# Power_Supply.net
KiCad netlist of a schematic drawn in Altium Designer
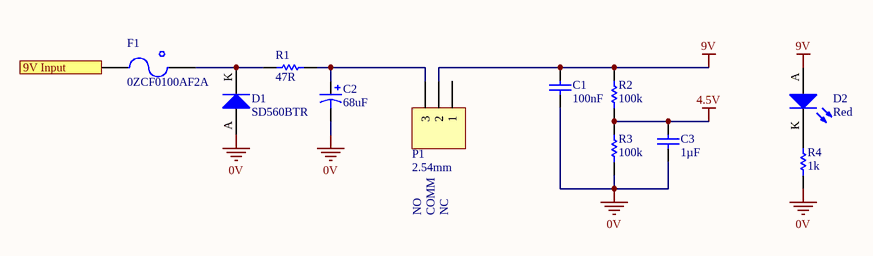
[diagram p0: Power Supply.SchDoc]

(export (version "E")
  (design (tool "Eeschema 10.0.6"))
  (components
    (comp (ref "C1")
      (value "100nF")
      (footprint "0805")
      (fields
        (field (name "PART NUMBER") "GCM21BR71H104KA37L")
        (field (name "TOLERANCE") "±10%")
        (field (name "MANUFACTURER") "muRata")
      )
      (libsource (lib "ts_20-standard-library") (part "Capacitor"))
    )
    (comp (ref "C2")
      (value "~")
      (footprint "2924")
      (fields
        (field (name "PART NUMBER") "TAJV686K035RNJ")
        (field (name "TOLERANCE") "10%")
        (field (name "MANUFACTURER") "AVX Corporation")
      )
      (libsource (lib "ts_20-standard-library") (part "Capacitor (Polarised)"))
    )
    (comp (ref "C3")
      (value "1µF")
      (footprint "0805")
      (fields
        (field (name "PART NUMBER") "GCM21BR71H105KA03L")
        (field (name "TOLERANCE") "±10%")
        (field (name "MANUFACTURER") "muRata")
      )
      (libsource (lib "ts_20-standard-library") (part "Capacitor"))
    )
    (comp (ref "D1")
      (value "SD560BTR")
      (footprint "SMB Diode")
      (description "1.2V_F 600V 5A SMB")
      (fields
        (field (name "MANUFACTURER") "SMC Diode Solutions")
        (field (name "DIGIKEY PART NUMBER") "1655-1530-2-ND")
      )
      (libsource (lib "ts_20-standard-library") (part "Diode"))
    )
    (comp (ref "D2")
      (value "Red")
      (footprint "0805 LED")
      (description "Red LED Indication - Discrete 1.75V 0805 (2012 Metric)")
      (fields (field (name "PART NUMBER") "SML-210LTT86") (field (name "MANUFACTURER") "ROHM Semiconductor"))
      (libsource (lib "ts_20-standard-library") (part "LED"))
    )
    (comp (ref "F1")
      (value "0ZCF0100AF2A")
      (footprint "2920")
      (description "PTC RESET FUSE 60V 1A 292")
      (fields
        (field (name "MANUFACTURER") "Littelfuse Inc.")
        (field (name "DIGIKEY PART NUMBER") "507-2070-1-ND")
      )
      (libsource (lib "ts_20-standard-library") (part "PTC Fuse"))
    )
    (comp (ref "P1")
      (value "2.54mm")
      (footprint "TH 2.54mm Header 1x3")
      (fields (field (name "PART NUMBER") "TH 2.54mm Header 1x3") (field (name "CONTACT") "NA"))
      (libsource (lib "ts_20-standard-connectors") (part "Header 1x3"))
    )
    (comp (ref "R1")
      (value "47R")
      (footprint "2512")
      (fields
        (field (name "PART NUMBER") "352147RFT")
        (field (name "MANUFACTURER") "TE Connectivity")
        (field (name "TOLERANCE") "0.01")
      )
      (libsource (lib "ts_20-standard-library") (part "Resistor"))
    )
    (comp (ref "R2")
      (value "100k")
      (footprint "0805")
      (fields
        (field (name "PART NUMBER") "RC0805FR07100KL")
        (field (name "MANUFACTURER") "YAGEO")
        (field (name "TOLERANCE") "0.01")
      )
      (libsource (lib "ts_20-standard-library") (part "Resistor"))
    )
    (comp (ref "R3")
      (value "100k")
      (footprint "0805")
      (fields
        (field (name "PART NUMBER") "RC0805FR07100KL")
        (field (name "MANUFACTURER") "YAGEO")
        (field (name "TOLERANCE") "0.01")
      )
      (libsource (lib "ts_20-standard-library") (part "Resistor"))
    )
    (comp (ref "R4")
      (value "1k")
      (footprint "0805")
      (fields
        (field (name "PART NUMBER") "RC0805FR071KL")
        (field (name "MANUFACTURER") "YAGEO")
        (field (name "TOLERANCE") "0.01")
      )
      (libsource (lib "ts_20-standard-library") (part "Resistor"))
    )
  )
  (nets
    (net (code "1") (name "/9V Input") (class "Default")
      (node (ref "F1") (pin "1") (pinfunction "1_1") (pintype "passive"))
    )
    (net (code "2") (name "0V") (class "Default")
      (node (ref "C1") (pin "2") (pinfunction "2_2") (pintype "passive"))
      (node (ref "C2") (pin "1") (pinfunction "1_1") (pintype "passive"))
      (node (ref "C3") (pin "1") (pinfunction "1_1") (pintype "passive"))
      (node (ref "D1") (pin "A") (pinfunction "A_A") (pintype "passive"))
      (node (ref "R3") (pin "1") (pinfunction "1_1") (pintype "passive"))
      (node (ref "R4") (pin "1") (pinfunction "1_1") (pintype "passive"))
    )
    (net (code "3") (name "4.5V") (class "Default")
      (node (ref "C3") (pin "2") (pinfunction "2_2") (pintype "passive"))
      (node (ref "R2") (pin "1") (pinfunction "1_1") (pintype "passive"))
      (node (ref "R3") (pin "2") (pinfunction "2_2") (pintype "passive"))
    )
    (net (code "4") (name "9V") (class "Default")
      (node (ref "C1") (pin "1") (pinfunction "1_1") (pintype "passive"))
      (node (ref "D2") (pin "A") (pinfunction "A_A") (pintype "passive"))
      (node (ref "P1") (pin "2") (pinfunction "2_2") (pintype "passive"))
      (node (ref "R2") (pin "2") (pinfunction "2_2") (pintype "passive"))
    )
    (net (code "5") (name "Net-(C2-Pad2)") (class "Default")
      (node (ref "C2") (pin "2") (pinfunction "2_2") (pintype "passive"))
      (node (ref "P1") (pin "3") (pinfunction "3_3") (pintype "passive"))
      (node (ref "R1") (pin "2") (pinfunction "2_2") (pintype "passive"))
    )
    (net (code "6") (name "Net-(D1-PadK)") (class "Default")
      (node (ref "D1") (pin "K") (pinfunction "K_K") (pintype "passive"))
      (node (ref "F1") (pin "2") (pinfunction "2_2") (pintype "passive"))
      (node (ref "R1") (pin "1") (pinfunction "1_1") (pintype "passive"))
    )
    (net (code "7") (name "Net-(D2-PadK)") (class "Default")
      (node (ref "D2") (pin "K") (pinfunction "K_K") (pintype "passive"))
      (node (ref "R4") (pin "2") (pinfunction "2_2") (pintype "passive"))
    )
    (net (code "8") (name "unconnected-(P1-Pad1)") (class "Default")
      (node (ref "P1") (pin "1") (pinfunction "1_1") (pintype "passive"))
    )
  )
)
